# midi-in-out-mini.net
KiCad netlist of a schematic drawn in EAGLE
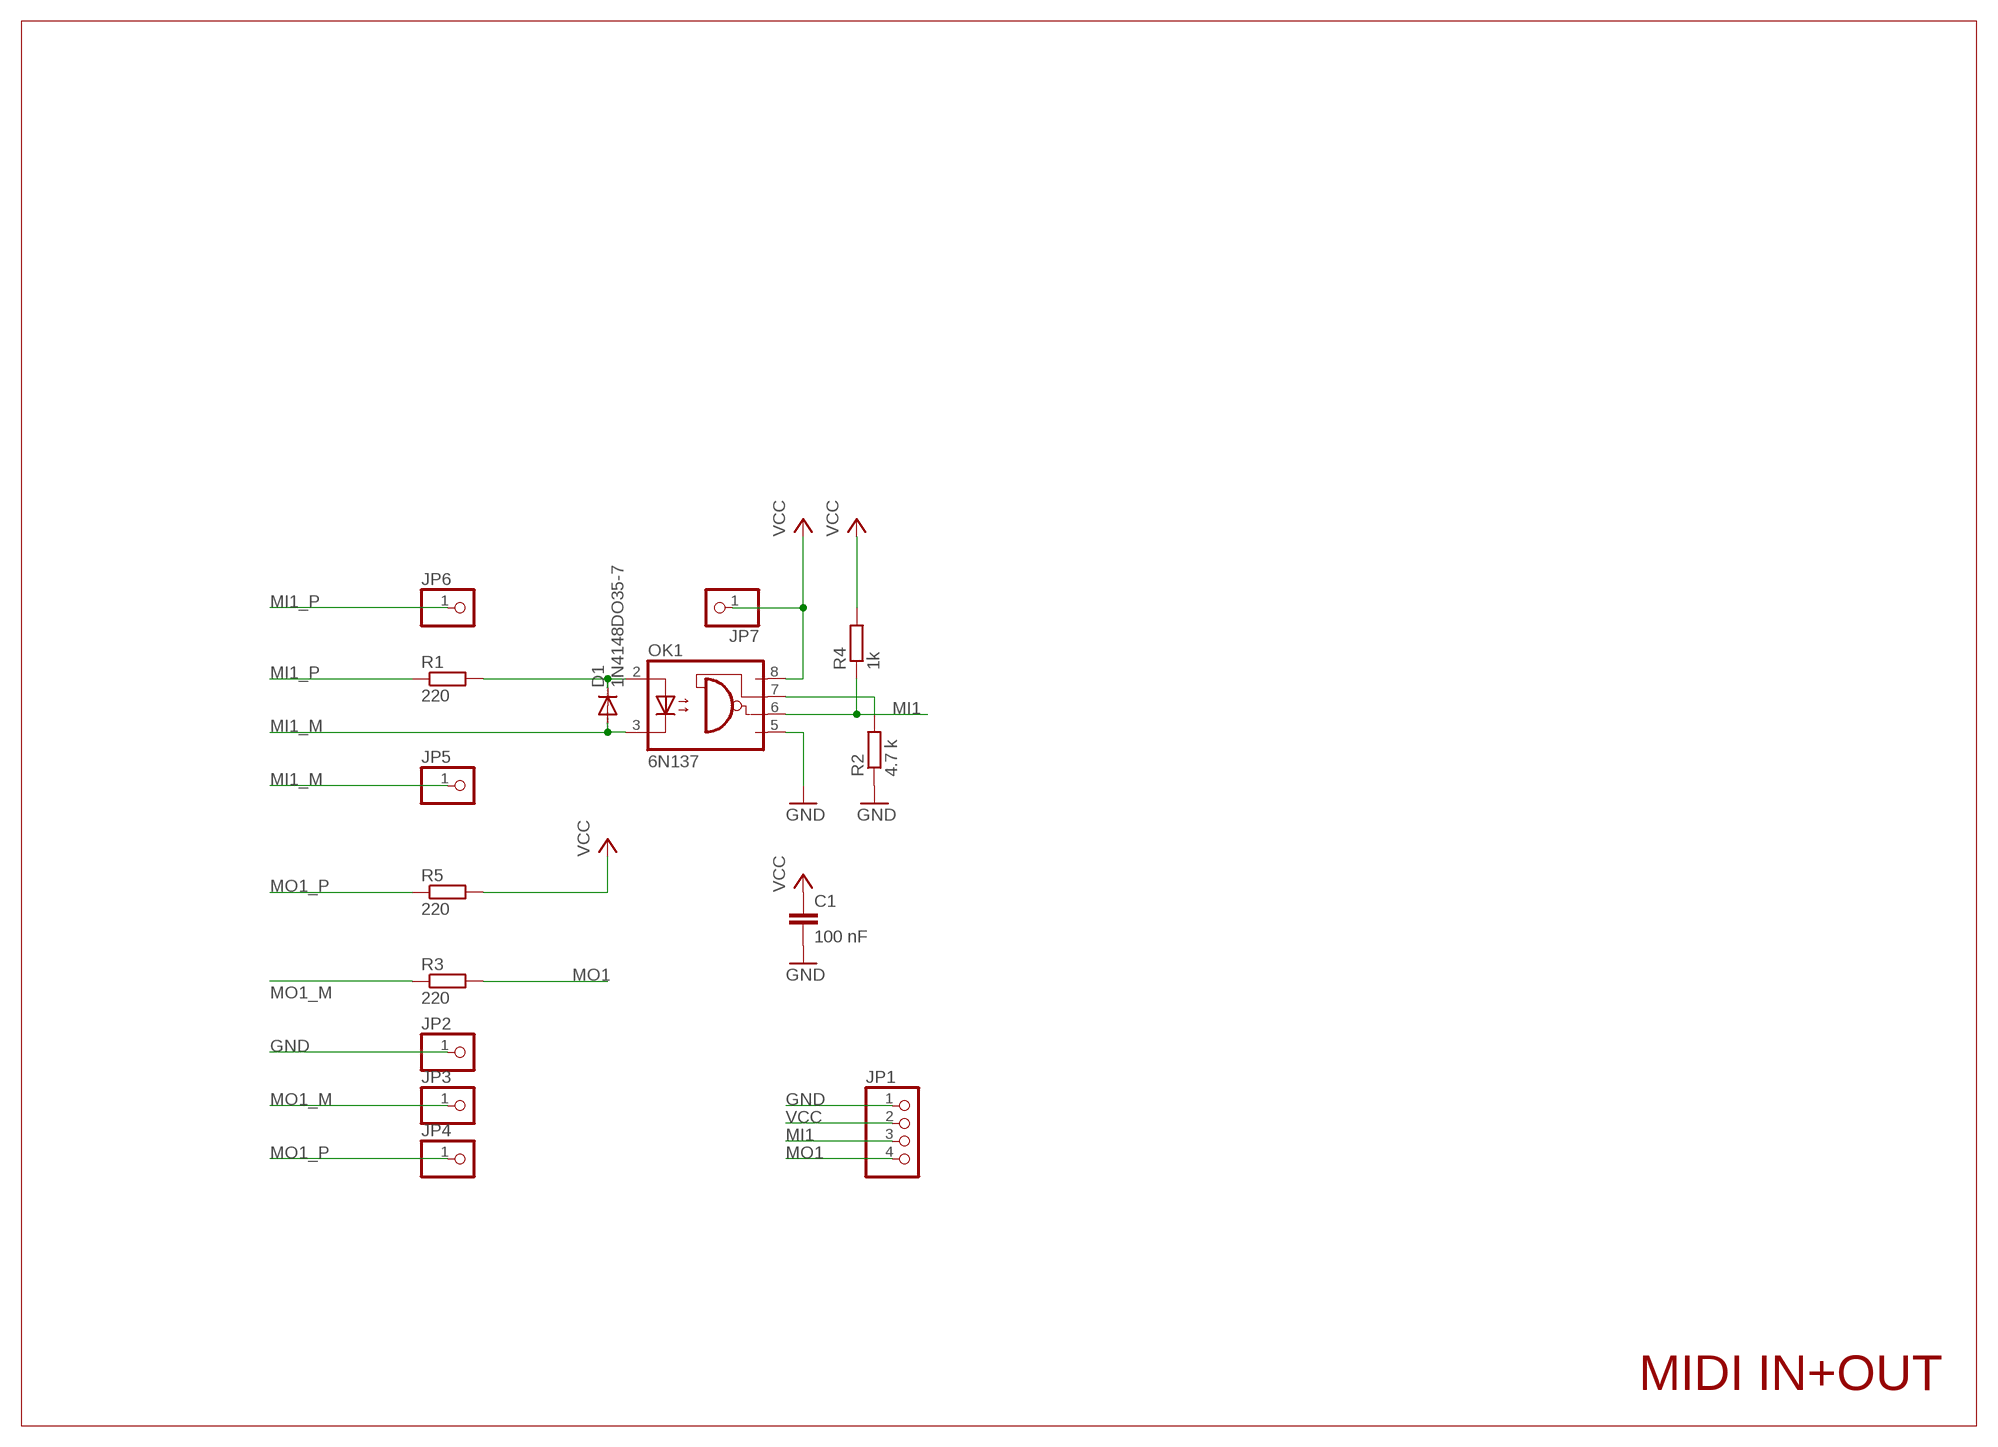
[diagram p0: schematic, sheet 1]

(export (version "E")
  (design (tool "Eeschema 10.0.6"))
  (components
    (comp (ref "C1")
      (value "100 nF")
      (footprint "eagle-import:C025-024X044")
      (libsource (lib "eagle-import") (part "C-EU025-024X044"))
    )
    (comp (ref "D1")
      (value "1N4148DO35-7")
      (footprint "eagle-import:DO35-7")
      (libsource (lib "eagle-import") (part "1N4148DO35-7"))
    )
    (comp (ref "JP1")
      (value "PINHD-1X4/90")
      (footprint "eagle-import:1X04_90")
      (libsource (lib "eagle-import") (part "PINHD-1X4/90"))
    )
    (comp (ref "JP2")
      (value "PINHD-1X1")
      (footprint "eagle-import:1X01")
      (libsource (lib "eagle-import") (part "PINHD-1X1"))
    )
    (comp (ref "JP3")
      (value "PINHD-1X1")
      (footprint "eagle-import:1X01")
      (libsource (lib "eagle-import") (part "PINHD-1X1"))
    )
    (comp (ref "JP4")
      (value "PINHD-1X1")
      (footprint "eagle-import:1X01")
      (libsource (lib "eagle-import") (part "PINHD-1X1"))
    )
    (comp (ref "JP5")
      (value "PINHD-1X1")
      (footprint "eagle-import:1X01")
      (libsource (lib "eagle-import") (part "PINHD-1X1"))
    )
    (comp (ref "JP6")
      (value "PINHD-1X1")
      (footprint "eagle-import:1X01")
      (libsource (lib "eagle-import") (part "PINHD-1X1"))
    )
    (comp (ref "JP7")
      (value "PINHD-1X1")
      (footprint "eagle-import:1X01")
      (libsource (lib "eagle-import") (part "PINHD-1X1"))
    )
    (comp (ref "OK1")
      (value "6N137")
      (footprint "eagle-import:DIL08")
      (libsource (lib "eagle-import") (part "6N137"))
    )
    (comp (ref "R1")
      (value "220")
      (footprint "eagle-import:0204_7")
      (libsource (lib "eagle-import") (part "R-EU_0204/7"))
    )
    (comp (ref "R2")
      (value "4.7 k")
      (footprint "eagle-import:0204_7")
      (libsource (lib "eagle-import") (part "R-EU_0204/7"))
    )
    (comp (ref "R3")
      (value "220")
      (footprint "eagle-import:0204_7")
      (libsource (lib "eagle-import") (part "R-EU_0204/7"))
    )
    (comp (ref "R4")
      (value "1k")
      (footprint "eagle-import:0204_7")
      (libsource (lib "eagle-import") (part "R-EU_0204/7"))
    )
    (comp (ref "R5")
      (value "220")
      (footprint "eagle-import:0204_7")
      (libsource (lib "eagle-import") (part "R-EU_0204/7"))
    )
  )
  (nets
    (net (code "1") (name "/MI1") (class "Default")
      (node (ref "JP1") (pin "3") (pinfunction "3_3") (pintype "passive"))
      (node (ref "OK1") (pin "6") (pinfunction "VO_6") (pintype "passive"))
      (node (ref "R4") (pin "1") (pinfunction "1_1") (pintype "passive"))
    )
    (net (code "2") (name "/MI1_M") (class "Default")
      (node (ref "D1") (pin "A") (pinfunction "A_A") (pintype "passive"))
      (node (ref "JP5") (pin "1") (pinfunction "1_1") (pintype "passive"))
      (node (ref "OK1") (pin "3") (pinfunction "C_3") (pintype "passive"))
    )
    (net (code "3") (name "/MI1_P") (class "Default")
      (node (ref "JP6") (pin "1") (pinfunction "1_1") (pintype "passive"))
      (node (ref "R1") (pin "1") (pinfunction "1_1") (pintype "passive"))
    )
    (net (code "4") (name "/MO1") (class "Default")
      (node (ref "JP1") (pin "4") (pinfunction "4_4") (pintype "passive"))
      (node (ref "R3") (pin "2") (pinfunction "2_2") (pintype "passive"))
    )
    (net (code "5") (name "/MO1_M") (class "Default")
      (node (ref "JP3") (pin "1") (pinfunction "1_1") (pintype "passive"))
      (node (ref "R3") (pin "1") (pinfunction "1_1") (pintype "passive"))
    )
    (net (code "6") (name "/MO1_P") (class "Default")
      (node (ref "JP4") (pin "1") (pinfunction "1_1") (pintype "passive"))
      (node (ref "R5") (pin "1") (pinfunction "1_1") (pintype "passive"))
    )
    (net (code "7") (name "GND") (class "Default")
      (node (ref "C1") (pin "2") (pinfunction "2_2") (pintype "passive"))
      (node (ref "JP1") (pin "1") (pinfunction "1_1") (pintype "passive"))
      (node (ref "JP2") (pin "1") (pinfunction "1_1") (pintype "passive"))
      (node (ref "OK1") (pin "5") (pinfunction "GND_5") (pintype "passive"))
      (node (ref "R2") (pin "1") (pinfunction "1_1") (pintype "passive"))
    )
    (net (code "8") (name "Net-(OK1-A)") (class "Default")
      (node (ref "D1") (pin "C") (pinfunction "C_C") (pintype "passive"))
      (node (ref "OK1") (pin "2") (pinfunction "A_2") (pintype "passive"))
      (node (ref "R1") (pin "2") (pinfunction "2_2") (pintype "passive"))
    )
    (net (code "9") (name "Net-(OK1-VE)") (class "Default")
      (node (ref "OK1") (pin "7") (pinfunction "VE_7") (pintype "passive"))
      (node (ref "R2") (pin "2") (pinfunction "2_2") (pintype "passive"))
    )
    (net (code "10") (name "VCC") (class "Default")
      (node (ref "C1") (pin "1") (pinfunction "1_1") (pintype "passive"))
      (node (ref "JP1") (pin "2") (pinfunction "2_2") (pintype "passive"))
      (node (ref "JP7") (pin "1") (pinfunction "1_1") (pintype "passive"))
      (node (ref "OK1") (pin "8") (pinfunction "VCC_8") (pintype "passive"))
      (node (ref "R4") (pin "2") (pinfunction "2_2") (pintype "passive"))
      (node (ref "R5") (pin "2") (pinfunction "2_2") (pintype "passive"))
    )
  )
)
